# Variac_output.net
KiCad netlist of a schematic drawn in EAGLE
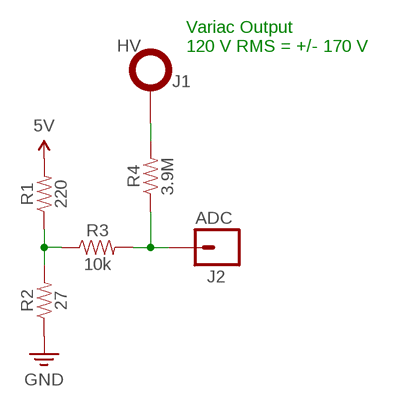
[diagram p0: schematic, sheet 1]

(export (version "E")
  (design (tool "Eeschema 10.0.6"))
  (components
    (comp (ref "J1")
      (value "HV")
      (footprint "eagle-import:LUG_SQUARE_M6")
      (libsource (lib "eagle-import") (part "TERMINAL_M6"))
    )
    (comp (ref "J2")
      (value "ADC")
      (footprint "eagle-import:1X01_2MM")
      (libsource (lib "eagle-import") (part "CONN_01PTH_2MM"))
    )
    (comp (ref "R1")
      (value "220")
      (footprint "eagle-import:AXIAL-0.3")
      (libsource (lib "eagle-import") (part "15KOHM-HORIZ-1/4W-5%"))
    )
    (comp (ref "R2")
      (value "27")
      (footprint "eagle-import:AXIAL-0.3")
      (libsource (lib "eagle-import") (part "15KOHM-HORIZ-1/4W-5%"))
    )
    (comp (ref "R3")
      (value "10k")
      (footprint "eagle-import:AXIAL-0.3")
      (libsource (lib "eagle-import") (part "15KOHM-HORIZ-1/4W-5%"))
    )
    (comp (ref "R4")
      (value "3.9M")
      (footprint "eagle-import:AXIAL-0.3")
      (libsource (lib "eagle-import") (part "15KOHM-HORIZ-1/4W-5%"))
    )
  )
  (nets
    (net (code "1") (name "5V") (class "Default")
      (node (ref "R1") (pin "P$2") (pinfunction "2_P$2") (pintype "passive"))
    )
    (net (code "2") (name "GND") (class "Default")
      (node (ref "R2") (pin "P$1") (pinfunction "1_P$1") (pintype "passive"))
    )
    (net (code "3") (name "Net-(R1-1)") (class "Default")
      (node (ref "R1") (pin "P$1") (pinfunction "1_P$1") (pintype "passive"))
      (node (ref "R2") (pin "P$2") (pinfunction "2_P$2") (pintype "passive"))
      (node (ref "R3") (pin "P$1") (pinfunction "1_P$1") (pintype "passive"))
    )
    (net (code "4") (name "Net-(R3-2)") (class "Default")
      (node (ref "J2") (pin "1") (pinfunction "1_1") (pintype "passive"))
      (node (ref "R3") (pin "P$2") (pinfunction "2_P$2") (pintype "passive"))
      (node (ref "R4") (pin "P$1") (pinfunction "1_P$1") (pintype "passive"))
    )
    (net (code "5") (name "Net-(R4-2)") (class "Default")
      (node (ref "J1") (pin "P$1") (pinfunction "P$1_P$1") (pintype "passive"))
      (node (ref "R4") (pin "P$2") (pinfunction "2_P$2") (pintype "passive"))
    )
  )
)
